# ADC_LoadCell_Board.net
KiCad netlist of a schematic drawn in EAGLE
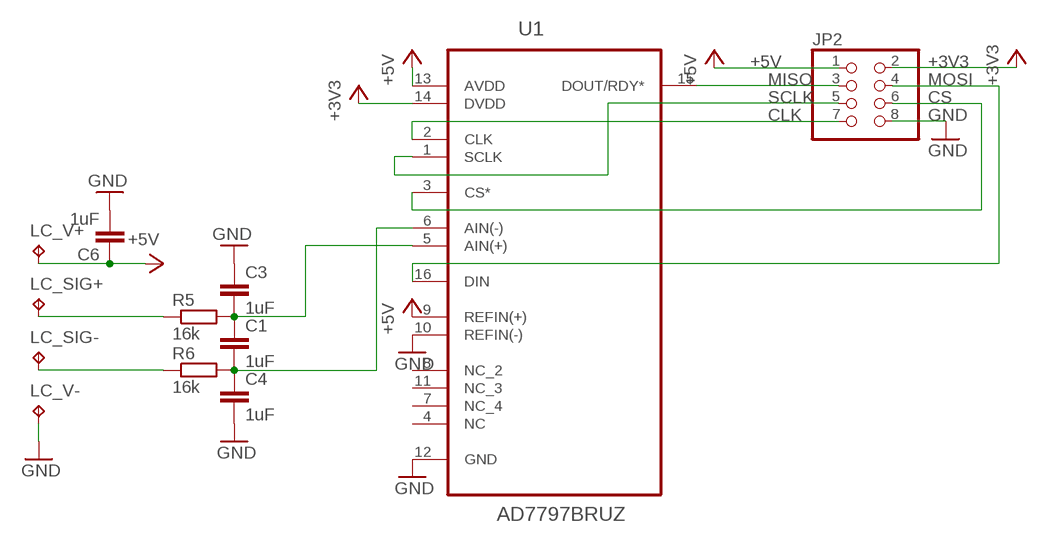
[diagram p0: schematic, sheet 1]

(export (version "E")
  (design (tool "Eeschema 10.0.6"))
  (components
    (comp (ref "C1")
      (value "1uF")
      (footprint "eagle-import:C0805")
      (libsource (lib "eagle-import") (part "C-EUC0805"))
    )
    (comp (ref "C3")
      (value "1uF")
      (footprint "eagle-import:C0805")
      (libsource (lib "eagle-import") (part "C-EUC0805"))
    )
    (comp (ref "C4")
      (value "1uF")
      (footprint "eagle-import:C0805")
      (libsource (lib "eagle-import") (part "C-EUC0805"))
    )
    (comp (ref "C6")
      (value "1uF")
      (footprint "eagle-import:C0805")
      (libsource (lib "eagle-import") (part "C-EUC0805"))
    )
    (comp (ref "JP2")
      (value "PINHD-2X4")
      (footprint "eagle-import:2X04")
      (libsource (lib "eagle-import") (part "PINHD-2X4"))
    )
    (comp (ref "LC_SIG+")
      (value "TPB1,27")
      (footprint "eagle-import:B1,27")
      (libsource (lib "eagle-import") (part "TPB1,27"))
    )
    (comp (ref "LC_SIG-")
      (value "TPB1,27")
      (footprint "eagle-import:B1,27")
      (libsource (lib "eagle-import") (part "TPB1,27"))
    )
    (comp (ref "LC_V+")
      (value "TPB1,27")
      (footprint "eagle-import:B1,27")
      (libsource (lib "eagle-import") (part "TPB1,27"))
    )
    (comp (ref "LC_V-")
      (value "TPB1,27")
      (footprint "eagle-import:B1,27")
      (libsource (lib "eagle-import") (part "TPB1,27"))
    )
    (comp (ref "R5")
      (value "16k")
      (footprint "eagle-import:R0805")
      (libsource (lib "eagle-import") (part "R-EU_R0805"))
    )
    (comp (ref "R6")
      (value "16k")
      (footprint "eagle-import:R0805")
      (libsource (lib "eagle-import") (part "R-EU_R0805"))
    )
    (comp (ref "U1")
      (value "AD7797BRUZ")
      (footprint "eagle-import:SOP65P640X120-16N")
      (libsource (lib "eagle-import") (part "AD7797BRUZ"))
    )
  )
  (nets
    (net (code "1") (name "+3V3") (class "Default")
      (node (ref "JP2") (pin "2") (pinfunction "2_2") (pintype "passive"))
      (node (ref "U1") (pin "14") (pinfunction "DVDD_14") (pintype "power_in"))
    )
    (net (code "2") (name "+5V") (class "Default")
      (node (ref "C6") (pin "1") (pinfunction "1_1") (pintype "passive"))
      (node (ref "JP2") (pin "1") (pinfunction "1_1") (pintype "passive"))
      (node (ref "LC_V+") (pin "TP") (pinfunction "TP_TP") (pintype "input"))
      (node (ref "U1") (pin "13") (pinfunction "AVDD_13") (pintype "power_in"))
      (node (ref "U1") (pin "9") (pinfunction "REFIN(+)_9") (pintype "input"))
    )
    (net (code "3") (name "/CLK") (class "Default")
      (node (ref "JP2") (pin "7") (pinfunction "7_7") (pintype "passive"))
      (node (ref "U1") (pin "2") (pinfunction "CLK_2") (pintype "bidirectional"))
    )
    (net (code "4") (name "/CS") (class "Default")
      (node (ref "JP2") (pin "6") (pinfunction "6_6") (pintype "passive"))
      (node (ref "U1") (pin "3") (pinfunction "CS*_3") (pintype "input"))
    )
    (net (code "5") (name "/MISO") (class "Default")
      (node (ref "JP2") (pin "3") (pinfunction "3_3") (pintype "passive"))
      (node (ref "U1") (pin "15") (pinfunction "DOUT/RDY*_15") (pintype "output"))
    )
    (net (code "6") (name "/MOSI") (class "Default")
      (node (ref "JP2") (pin "4") (pinfunction "4_4") (pintype "passive"))
      (node (ref "U1") (pin "16") (pinfunction "DIN_16") (pintype "input"))
    )
    (net (code "7") (name "/SCLK") (class "Default")
      (node (ref "JP2") (pin "5") (pinfunction "5_5") (pintype "passive"))
      (node (ref "U1") (pin "1") (pinfunction "SCLK_1") (pintype "input"))
    )
    (net (code "8") (name "GND") (class "Default")
      (node (ref "C3") (pin "1") (pinfunction "1_1") (pintype "passive"))
      (node (ref "C4") (pin "2") (pinfunction "2_2") (pintype "passive"))
      (node (ref "C6") (pin "2") (pinfunction "2_2") (pintype "passive"))
      (node (ref "JP2") (pin "8") (pinfunction "8_8") (pintype "passive"))
      (node (ref "LC_V-") (pin "TP") (pinfunction "TP_TP") (pintype "input"))
      (node (ref "U1") (pin "10") (pinfunction "REFIN(-)_10") (pintype "input"))
      (node (ref "U1") (pin "12") (pinfunction "GND_12") (pintype "passive"))
    )
    (net (code "9") (name "Net-(LC_SIG+-PadTP)") (class "Default")
      (node (ref "LC_SIG+") (pin "TP") (pinfunction "TP_TP") (pintype "input"))
      (node (ref "R5") (pin "1") (pinfunction "1_1") (pintype "passive"))
    )
    (net (code "10") (name "Net-(LC_SIG--PadTP)") (class "Default")
      (node (ref "LC_SIG-") (pin "TP") (pinfunction "TP_TP") (pintype "input"))
      (node (ref "R6") (pin "1") (pinfunction "1_1") (pintype "passive"))
    )
    (net (code "11") (name "Net-(U1-AIN(+))") (class "Default")
      (node (ref "C1") (pin "1") (pinfunction "1_1") (pintype "passive"))
      (node (ref "C3") (pin "2") (pinfunction "2_2") (pintype "passive"))
      (node (ref "R5") (pin "2") (pinfunction "2_2") (pintype "passive"))
      (node (ref "U1") (pin "5") (pinfunction "AIN(+)_5") (pintype "input"))
    )
    (net (code "12") (name "Net-(U1-AIN(-))") (class "Default")
      (node (ref "C1") (pin "2") (pinfunction "2_2") (pintype "passive"))
      (node (ref "C4") (pin "1") (pinfunction "1_1") (pintype "passive"))
      (node (ref "R6") (pin "2") (pinfunction "2_2") (pintype "passive"))
      (node (ref "U1") (pin "6") (pinfunction "AIN(-)_6") (pintype "input"))
    )
    (net (code "13") (name "unconnected-(U1-NC-Pad4)") (class "Default")
      (node (ref "U1") (pin "4") (pinfunction "NC_4") (pintype "no_connect"))
    )
    (net (code "14") (name "unconnected-(U1-NC_2-Pad8)") (class "Default")
      (node (ref "U1") (pin "8") (pinfunction "NC_2_8") (pintype "no_connect"))
    )
    (net (code "15") (name "unconnected-(U1-NC_3-Pad11)") (class "Default")
      (node (ref "U1") (pin "11") (pinfunction "NC_3_11") (pintype "no_connect"))
    )
    (net (code "16") (name "unconnected-(U1-NC_4-Pad7)") (class "Default")
      (node (ref "U1") (pin "7") (pinfunction "NC_4_7") (pintype "no_connect"))
    )
  )
)
